# Flight_sensor.net
KiCad netlist of a schematic drawn in Altium Designer
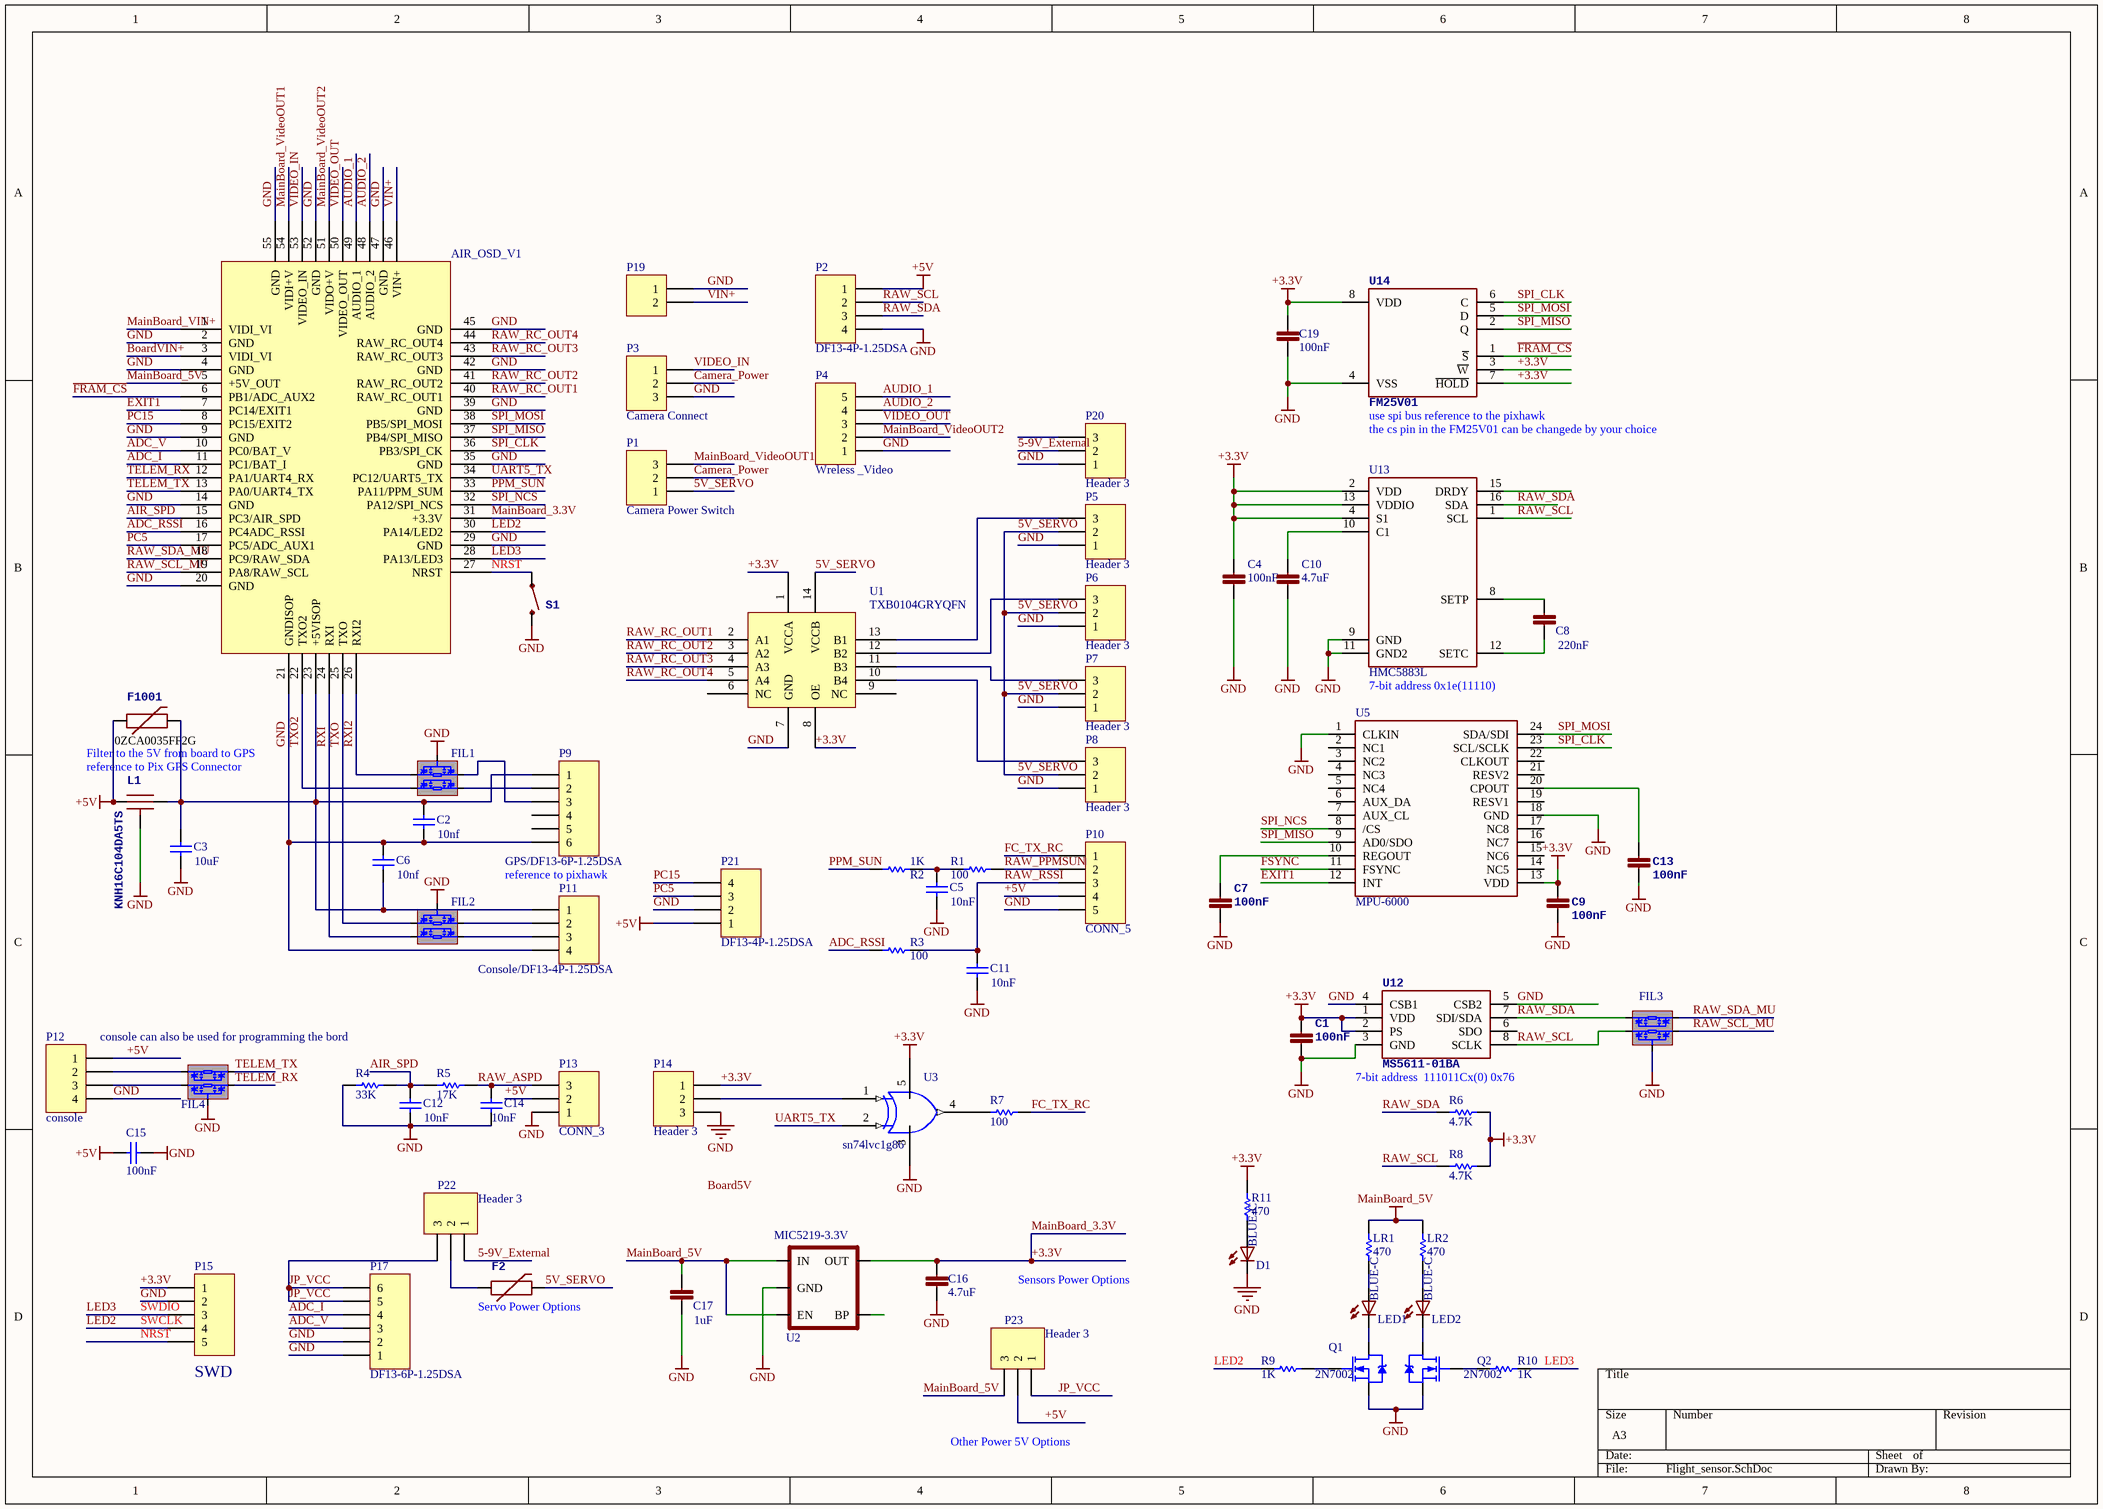
[diagram p0: Flight_sensor.SchDoc]

(export (version "E")
  (design (tool "Eeschema 10.0.6"))
  (components
    (comp (ref "AIR_OSD_V1")
      (value "AIR_OSD_V1")
      (footprint "AIR_OSD_CON")
      (libsource (lib "Schlib") (part "AIR_OSD_V1"))
    )
    (comp (ref "C1") (value "100nF") (footprint "0402-CAP") (libsource (lib "") (part "CAP0402-CAP_1")))
    (comp (ref "C2")
      (value "10nf")
      (footprint "0402-CAP")
      (description "Capacitor")
      (libsource (lib "Miscellaneous Devices") (part "Cap"))
    )
    (comp (ref "C3")
      (value "10uF")
      (footprint "0805")
      (description "Capacitor")
      (libsource (lib "Miscellaneous Devices") (part "Cap"))
    )
    (comp (ref "C4") (value "100nF") (footprint "0402-CAP") (libsource (lib "SparkFun") (part "CAP0402-CAP")))
    (comp (ref "C5")
      (value "10nF")
      (footprint "0402-CAP")
      (description "Capacitor")
      (libsource (lib "Miscellaneous Devices") (part "Cap"))
    )
    (comp (ref "C6")
      (value "10nf")
      (footprint "0402-CAP")
      (description "Capacitor")
      (libsource (lib "Miscellaneous Devices") (part "Cap"))
    )
    (comp (ref "C7") (value "100nF") (footprint "0402-CAP") (libsource (lib "") (part "CAP0402-CAP_1")))
    (comp (ref "C8") (value "220nF") (footprint "0402-CAP") (libsource (lib "SparkFun") (part "CAP0402-CAP")))
    (comp (ref "C9") (value "100nF") (footprint "0402-CAP") (libsource (lib "") (part "CAP0402-CAP_1")))
    (comp (ref "C10") (value "4.7uF") (footprint "0805") (libsource (lib "SparkFun") (part "CAP0805")))
    (comp (ref "C11")
      (value "10nF")
      (footprint "0402-CAP")
      (description "Capacitor")
      (libsource (lib "Miscellaneous Devices") (part "Cap"))
    )
    (comp (ref "C12")
      (value "10nF")
      (footprint "0402-CAP")
      (description "Capacitor")
      (libsource (lib "Miscellaneous Devices") (part "Cap"))
    )
    (comp (ref "C13") (value "100nF") (footprint "0402-CAP") (libsource (lib "") (part "CAP0402-CAP_1")))
    (comp (ref "C14")
      (value "10nF")
      (footprint "0402-CAP")
      (description "Capacitor")
      (libsource (lib "Miscellaneous Devices") (part "Cap"))
    )
    (comp (ref "C15")
      (value "100nF")
      (footprint "0402-CAP")
      (description "Capacitor")
      (libsource (lib "Miscellaneous Devices") (part "Cap"))
    )
    (comp (ref "C16") (value "4.7uF") (footprint "0805") (libsource (lib "SparkFun") (part "CAP0402-CAP")))
    (comp (ref "C17") (value "1uF") (footprint "0805") (libsource (lib "SparkFun") (part "CAP0402-CAP")))
    (comp (ref "C19") (value "100nF") (footprint "0402-CAP") (libsource (lib "") (part "CAP0402-CAP_1")))
    (comp (ref "D1") (value "BLUE-C") (footprint "LED-0603") (libsource (lib "SparkFun") (part "LED0603")))
    (comp (ref "F2")
      (value "0ZCA0035FF2G")
      (footprint "PTC-1206")
      (description "<b>Resettable Fuse PTC</b>\nResettable Fuse. Spark Fun Electronics SKU : COM-08357")
      (fields (field (name ">NAME") "F2"))
      (libsource (lib "pixhawk2") (part "PTCSMD"))
    )
    (comp (ref "F1001")
      (value "0ZCA0035FF2G")
      (footprint "PTC-1206")
      (description "<b>Resettable Fuse PTC</b>\nResettable Fuse. Spark Fun Electronics SKU : COM-08357")
      (fields (field (name ">NAME") "F1001"))
      (libsource (lib "pixhawk2") (part "PTCSMD"))
    )
    (comp (ref "FIL1")
      (value "IP4256CZ5-W,115")
      (footprint "SOT-665")
      (description "IP4256CZ5-W,115 2 channel, 100R, 30pF, RF ESD Filter")
      (fields
        (field (name "MANUFACTURER") "Generic Components")
        (field (name "PUBLISHER") "The OpenPilot Project")
      )
      (libsource (lib "OpenPilot") (part "RF Filter 100R 30pF"))
    )
    (comp (ref "FIL2")
      (value "IP4256CZ5-W,115")
      (footprint "SOT-665")
      (description "IP4256CZ5-W,115 2 channel, 100R, 30pF, RF ESD Filter")
      (fields
        (field (name "MANUFACTURER") "Generic Components")
        (field (name "PUBLISHER") "The OpenPilot Project")
      )
      (libsource (lib "OpenPilot") (part "RF Filter 100R 30pF"))
    )
    (comp (ref "FIL3")
      (value "IP4256CZ5-W,115")
      (footprint "SOT-665")
      (description "IP4256CZ5-W,115 2 channel, 100R, 30pF, RF ESD Filter")
      (fields
        (field (name "MANUFACTURER") "Generic Components")
        (field (name "PUBLISHER") "The OpenPilot Project")
      )
      (libsource (lib "OpenPilot") (part "RF Filter 100R 30pF"))
    )
    (comp (ref "FIL4")
      (value "IP4256CZ5-W,115")
      (footprint "SOT-665")
      (description "IP4256CZ5-W,115 2 channel, 100R, 30pF, RF ESD Filter")
      (fields
        (field (name "MANUFACTURER") "Generic Components")
        (field (name "PUBLISHER") "The OpenPilot Project")
      )
      (libsource (lib "OpenPilot") (part "RF Filter 100R 30pF"))
    )
    (comp (ref "L1")
      (value "KNH16C104DA5TS")
      (footprint "KYOCERA-KNH16-DA")
      (description "Kyocera KNH16C104DA5TS EMI filter")
      (fields (field (name ">NAME") "L1") (field (name ">VALUE") "KNH16C104DA5TS"))
      (libsource (lib "pixhawk2") (part "KNH16C104DA5TS"))
    )
    (comp (ref "LED1") (value "BLUE-C") (footprint "LED-0603") (libsource (lib "SparkFun") (part "LED0603")))
    (comp (ref "LED2") (value "BLUE-C") (footprint "LED-0603") (libsource (lib "SparkFun") (part "LED0603")))
    (comp (ref "LR1")
      (value "470")
      (footprint "0402-RES")
      (description "Resistor")
      (libsource (lib "原理图库") (part "Res1"))
    )
    (comp (ref "LR2")
      (value "470")
      (footprint "0402-RES")
      (description "Resistor")
      (libsource (lib "原理图库") (part "Res1"))
    )
    (comp (ref "P1")
      (value "Camera Power Switch")
      (footprint "3X1-NS")
      (description "Header, 3-Pin")
      (fields (field (name "PUBLISHER") "Altium Limited"))
      (libsource (lib "") (part "Header 3_3"))
    )
    (comp (ref "P2")
      (value "DF13-4P-1.25DSA")
      (footprint "DF13-4P-1.25DSA")
      (description "Header, 4-Pin")
      (fields (field (name "PUBLISHER") "Altium Limited"))
      (libsource (lib "Miscellaneous Connectors") (part "Header 4"))
    )
    (comp (ref "P3")
      (value "Camera Connect")
      (footprint "HDR1X3")
      (description "Header, 3-Pin")
      (fields (field (name "PUBLISHER") "Altium Limited"))
      (libsource (lib "") (part "Header 3_2"))
    )
    (comp (ref "P4")
      (value "Wreless _Video")
      (footprint "HDR1X5")
      (description "Header, 5-Pin")
      (libsource (lib "") (part "Header 5_1"))
    )
    (comp (ref "P5")
      (value "Header 3")
      (footprint "HDR1X3")
      (description "Header, 3-Pin")
      (fields (field (name "PUBLISHER") "Altium Limited"))
      (libsource (lib "Miscellaneous Connectors") (part "Header 3"))
    )
    (comp (ref "P6")
      (value "Header 3")
      (footprint "HDR1X3")
      (description "Header, 3-Pin")
      (fields (field (name "PUBLISHER") "Altium Limited"))
      (libsource (lib "Miscellaneous Connectors") (part "Header 3"))
    )
    (comp (ref "P7")
      (value "Header 3")
      (footprint "HDR1X3")
      (description "Header, 3-Pin")
      (fields (field (name "PUBLISHER") "Altium Limited"))
      (libsource (lib "Miscellaneous Connectors") (part "Header 3"))
    )
    (comp (ref "P8")
      (value "Header 3")
      (footprint "HDR1X3")
      (description "Header, 3-Pin")
      (fields (field (name "PUBLISHER") "Altium Limited"))
      (libsource (lib "Miscellaneous Connectors") (part "Header 3"))
    )
    (comp (ref "P9")
      (value "GPS/DF13-6P-1.25DSA")
      (footprint "PIXHAWK2_DF13-6P-1.25DSA")
      (description "Header, 6-Pin")
      (fields (field (name "PUBLISHER") "Altium Limited"))
      (libsource (lib "") (part "Header 6_1"))
    )
    (comp (ref "P10")
      (value "CONN_5")
      (footprint "DF13-5P-1.25DSA")
      (description "Header, 5-Pin")
      (libsource (lib "Miscellaneous Connectors") (part "Header 5"))
    )
    (comp (ref "P11")
      (value "Console/DF13-4P-1.25DSA")
      (footprint "DF13-4P-1.25DSA")
      (description "Header, 4-Pin")
      (fields (field (name "PUBLISHER") "Altium Limited"))
      (libsource (lib "") (part "Header 4_1"))
    )
    (comp (ref "P12")
      (value "console")
      (footprint "DF13-4P-1.25DSA")
      (description "Header, 4-Pin")
      (fields (field (name "PUBLISHER") "Altium Limited"))
      (libsource (lib "Miscellaneous Connectors") (part "Header 4"))
    )
    (comp (ref "P13")
      (value "CONN_3")
      (footprint "HDR1X3")
      (description "Header, 3-Pin")
      (libsource (lib "Miscellaneous Connectors") (part "Header 3"))
    )
    (comp (ref "P14")
      (value "Header 3")
      (footprint "HDR1X3")
      (description "Header, 3-Pin")
      (fields (field (name "PUBLISHER") "Altium Limited"))
      (libsource (lib "") (part "Header 3_2"))
    )
    (comp (ref "P15")
      (value "SWD")
      (footprint "DF13-5P-1.25DSA")
      (description "Header, 5-Pin")
      (libsource (lib "Miscellaneous Connectors") (part "Header 5"))
    )
    (comp (ref "P17")
      (value "DF13-6P-1.25DSA")
      (footprint "PIXHAWK2_DF13-6P-1.25DSA")
      (description "Header, 6-Pin")
      (libsource (lib "Miscellaneous Connectors") (part "Header 6"))
    )
    (comp (ref "P19")
      (value "Header 2")
      (footprint "HDR1X2")
      (description "接插件")
      (fields (field (name "PUBLISHER") "Altium Limited"))
      (libsource (lib "Miscellaneous Connectors") (part "Header 2"))
    )
    (comp (ref "P20")
      (value "Header 3")
      (footprint "HDR1X3")
      (description "Header, 3-Pin")
      (fields (field (name "PUBLISHER") "Altium Limited"))
      (libsource (lib "Miscellaneous Connectors") (part "Header 3"))
    )
    (comp (ref "P21")
      (value "DF13-4P-1.25DSA")
      (footprint "HDR1X4")
      (description "Header, 4-Pin")
      (fields (field (name "PUBLISHER") "Altium Limited"))
      (libsource (lib "") (part "Header 4_2"))
    )
    (comp (ref "P22")
      (value "Header 3")
      (footprint "0402-S")
      (description "Header, 3-Pin")
      (fields (field (name "PUBLISHER") "Altium Limited"))
      (libsource (lib "") (part "Header 3_1"))
    )
    (comp (ref "P23")
      (value "Header 3")
      (footprint "0402-S")
      (description "Header, 3-Pin")
      (fields (field (name "PUBLISHER") "Altium Limited"))
      (libsource (lib "") (part "Header 3_1"))
    )
    (comp (ref "Q1")
      (value "2N7002")
      (footprint "2N7002")
      (description "CQ-IRF840")
      (libsource (lib "晶体管") (part "IRF840"))
    )
    (comp (ref "Q2")
      (value "2N7002")
      (footprint "2N7002")
      (description "CQ-IRF840")
      (libsource (lib "晶体管") (part "IRF840"))
    )
    (comp (ref "R1")
      (value "100")
      (footprint "0402-RES")
      (description "Resistor")
      (libsource (lib "Miscellaneous Devices") (part "Res1"))
    )
    (comp (ref "R2")
      (value "1K")
      (footprint "0402-RES")
      (description "Resistor")
      (libsource (lib "Miscellaneous Devices") (part "Res1"))
    )
    (comp (ref "R3")
      (value "100")
      (footprint "0402-RES")
      (description "Resistor")
      (libsource (lib "Miscellaneous Devices") (part "Res1"))
    )
    (comp (ref "R4")
      (value "33K")
      (footprint "0402-RES")
      (description "Resistor")
      (libsource (lib "Miscellaneous Devices") (part "Res1"))
    )
    (comp (ref "R5")
      (value "17K")
      (footprint "0402-RES")
      (description "Resistor")
      (libsource (lib "Miscellaneous Devices") (part "Res1"))
    )
    (comp (ref "R6")
      (value "4.7K")
      (footprint "0402-RES")
      (description "Resistor")
      (libsource (lib "Miscellaneous Devices") (part "Res1"))
    )
    (comp (ref "R7")
      (value "100")
      (footprint "0402-RES")
      (description "Resistor")
      (libsource (lib "原理图库") (part "Res1"))
    )
    (comp (ref "R8")
      (value "4.7K")
      (footprint "0402-RES")
      (description "Resistor")
      (libsource (lib "Miscellaneous Devices") (part "Res1"))
    )
    (comp (ref "R9")
      (value "1K")
      (footprint "0402-RES")
      (description "Resistor")
      (libsource (lib "Miscellaneous Devices") (part "Res1"))
    )
    (comp (ref "R10")
      (value "1K")
      (footprint "0402-RES")
      (description "Resistor")
      (libsource (lib "Miscellaneous Devices") (part "Res1"))
    )
    (comp (ref "R11")
      (value "470")
      (footprint "0402-RES")
      (description "Resistor")
      (libsource (lib "原理图库") (part "Res1"))
    )
    (comp (ref "S1")
      (value "RESET")
      (footprint "EVQP7J01K")
      (libsource (lib "pixhawk2") (part "SWITCH-MOMENTARY-2"))
    )
    (comp (ref "U1")
      (value "TXB0104GRYQFN")
      (footprint "RGY(S-PVQFN-N14)")
      (libsource (lib "Schlib") (part "TXB0104UQFN"))
    )
    (comp (ref "U2")
      (value "MIC5219-3.3V")
      (footprint "SOT23-5")
      (libsource (lib "SparkFun") (part "V_REG_LDOSMD"))
    )
    (comp (ref "U3") (value "sn74lvc1g86") (libsource (lib "FlightSensorPrj") (part "sn74lvc1g86")))
    (comp (ref "U5")
      (value "MPU-6000")
      (footprint "MPU6000")
      (libsource (lib "3DRobotics_Master_Library") (part "MPU-3000"))
    )
    (comp (ref "U12")
      (value "MS5611-01BA")
      (footprint "MS5611-01BA")
      (libsource (lib "3DRobotics") (part "MS5611-01BA"))
    )
    (comp (ref "U13")
      (value "HMC5883L")
      (footprint "LPCC16")
      (libsource (lib "3DRobotics") (part "HMC5883L"))
    )
    (comp (ref "U14")
      (value "FM25V01")
      (footprint "SO08")
      (description "<b>FM25V01 128Kb Serial 3V F-RAM Memory</b>")
      (fields
        (field (name "PARTNO") "FM25V01-G")
        (field (name ">NAME") "U14")
        (field (name ">VALUE") "FM25V01")
      )
      (libsource (lib "pixhawk2") (part "FM25V01"))
    )
  )
  (nets
    (net (code "1") (name "+3.3V") (class "Default")
      (node (ref "AIR_OSD_V1") (pin "31") (pinfunction "+3.3V_31") (pintype "passive"))
      (node (ref "C1") (pin "2") (pinfunction "2_2") (pintype "passive"))
      (node (ref "C16") (pin "1") (pinfunction "1_1") (pintype "passive"))
      (node (ref "C19") (pin "2") (pinfunction "2_2") (pintype "passive"))
      (node (ref "C4") (pin "1") (pinfunction "1_1") (pintype "passive"))
      (node (ref "C9") (pin "2") (pinfunction "2_2") (pintype "passive"))
      (node (ref "P14") (pin "1") (pinfunction "1_1") (pintype "passive"))
      (node (ref "P15") (pin "1") (pinfunction "1_1") (pintype "passive"))
      (node (ref "R11") (pin "2") (pinfunction "2_2") (pintype "passive"))
      (node (ref "R6") (pin "1") (pinfunction "1_1") (pintype "passive"))
      (node (ref "R8") (pin "1") (pinfunction "1_1") (pintype "passive"))
      (node (ref "U1") (pin "1") (pinfunction "VCCA_1") (pintype "passive"))
      (node (ref "U1") (pin "8") (pinfunction "OE_8") (pintype "passive"))
      (node (ref "U12") (pin "1") (pinfunction "VDD_1") (pintype "passive"))
      (node (ref "U12") (pin "2") (pinfunction "PS_2") (pintype "passive"))
      (node (ref "U13") (pin "13") (pinfunction "VDDIO_13") (pintype "passive"))
      (node (ref "U13") (pin "2") (pinfunction "VDD_2") (pintype "passive"))
      (node (ref "U13") (pin "4") (pinfunction "S1_4") (pintype "passive"))
      (node (ref "U14") (pin "3") (pinfunction "~{W}_3") (pintype "passive"))
      (node (ref "U14") (pin "7") (pinfunction "~{HOLD}_7") (pintype "passive"))
      (node (ref "U14") (pin "8") (pinfunction "VDD_8") (pintype "passive"))
      (node (ref "U2") (pin "5") (pinfunction "OUT_5") (pintype "passive"))
      (node (ref "U3") (pin "5") (pinfunction "VDD_5") (pintype "power_in"))
      (node (ref "U5") (pin "13") (pinfunction "VDD_13") (pintype "passive"))
    )
    (net (code "2") (name "+5V") (class "Default")
      (node (ref "C15") (pin "2") (pinfunction "2_2") (pintype "passive"))
      (node (ref "F1001") (pin "1") (pinfunction "1_1") (pintype "passive"))
      (node (ref "L1") (pin "P$1") (pinfunction "P$1_P$1") (pintype "passive"))
      (node (ref "P10") (pin "4") (pinfunction "4_4") (pintype "passive"))
      (node (ref "P12") (pin "1") (pinfunction "1_1") (pintype "passive"))
      (node (ref "P13") (pin "2") (pinfunction "2_2") (pintype "passive"))
      (node (ref "P2") (pin "1") (pinfunction "1_1") (pintype "passive"))
      (node (ref "P21") (pin "1") (pinfunction "1_1") (pintype "passive"))
      (node (ref "P23") (pin "2") (pinfunction "2_2") (pintype "passive"))
    )
    (net (code "3") (name "/5-9V_External") (class "Default")
      (node (ref "P20") (pin "2") (pinfunction "2_2") (pintype "passive"))
      (node (ref "P22") (pin "1") (pinfunction "1_1") (pintype "passive"))
    )
    (net (code "4") (name "/5V_SERVO") (class "Default")
      (node (ref "F2") (pin "2") (pinfunction "2_2") (pintype "passive"))
      (node (ref "P1") (pin "1") (pinfunction "1_1") (pintype "passive"))
      (node (ref "P5") (pin "2") (pinfunction "2_2") (pintype "passive"))
      (node (ref "P6") (pin "2") (pinfunction "2_2") (pintype "passive"))
      (node (ref "P7") (pin "2") (pinfunction "2_2") (pintype "passive"))
      (node (ref "P8") (pin "2") (pinfunction "2_2") (pintype "passive"))
      (node (ref "U1") (pin "14") (pinfunction "VCCB_14") (pintype "passive"))
    )
    (net (code "5") (name "/ADC_I") (class "Default")
      (node (ref "AIR_OSD_V1") (pin "11") (pinfunction "PC1/BAT_I_11") (pintype "passive"))
      (node (ref "P17") (pin "4") (pinfunction "4_4") (pintype "passive"))
    )
    (net (code "6") (name "/ADC_RSSI") (class "Default")
      (node (ref "AIR_OSD_V1") (pin "16") (pinfunction "PC4ADC_RSSI_16") (pintype "passive"))
      (node (ref "R3") (pin "2") (pinfunction "2_2") (pintype "passive"))
    )
    (net (code "7") (name "/ADC_V") (class "Default")
      (node (ref "AIR_OSD_V1") (pin "10") (pinfunction "PC0/BAT_V_10") (pintype "passive"))
      (node (ref "P17") (pin "3") (pinfunction "3_3") (pintype "passive"))
    )
    (net (code "8") (name "/AIR_SPD") (class "Default")
      (node (ref "AIR_OSD_V1") (pin "15") (pinfunction "PC3/AIR_SPD_15") (pintype "passive"))
      (node (ref "C12") (pin "2") (pinfunction "2_2") (pintype "passive"))
      (node (ref "R4") (pin "1") (pinfunction "1_1") (pintype "passive"))
      (node (ref "R5") (pin "2") (pinfunction "2_2") (pintype "passive"))
    )
    (net (code "9") (name "/AUDIO_1") (class "Default")
      (node (ref "AIR_OSD_V1") (pin "49") (pinfunction "AUDIO_1_49") (pintype "passive"))
      (node (ref "P4") (pin "5") (pinfunction "5_5") (pintype "passive"))
    )
    (net (code "10") (name "/AUDIO_2") (class "Default")
      (node (ref "AIR_OSD_V1") (pin "48") (pinfunction "AUDIO_2_48") (pintype "passive"))
      (node (ref "P4") (pin "4") (pinfunction "4_4") (pintype "passive"))
    )
    (net (code "12") (name "/BoardVIN+") (class "Default")
      (node (ref "AIR_OSD_V1") (pin "3") (pinfunction "VIDI_VI_3") (pintype "passive"))
    )
    (net (code "13") (name "/Camera_Power") (class "Default")
      (node (ref "P1") (pin "2") (pinfunction "2_2") (pintype "passive"))
      (node (ref "P3") (pin "2") (pinfunction "2_2") (pintype "passive"))
    )
    (net (code "14") (name "/EXIT1") (class "Default")
      (node (ref "AIR_OSD_V1") (pin "7") (pinfunction "PC14/EXIT1_7") (pintype "passive"))
      (node (ref "U5") (pin "12") (pinfunction "INT_12") (pintype "passive"))
    )
    (net (code "15") (name "/FC_TX_RC") (class "Default")
      (node (ref "P10") (pin "1") (pinfunction "1_1") (pintype "passive"))
      (node (ref "R7") (pin "1") (pinfunction "1_1") (pintype "passive"))
    )
    (net (code "16") (name "/FSYNC") (class "Default")
      (node (ref "U5") (pin "11") (pinfunction "FSYNC_11") (pintype "passive"))
    )
    (net (code "17") (name "/JP_VCC") (class "Default")
      (node (ref "P17") (pin "5") (pinfunction "5_5") (pintype "passive"))
      (node (ref "P17") (pin "6") (pinfunction "6_6") (pintype "passive"))
      (node (ref "P22") (pin "3") (pinfunction "3_3") (pintype "passive"))
      (node (ref "P23") (pin "1") (pinfunction "1_1") (pintype "passive"))
    )
    (net (code "18") (name "/LED2") (class "Default")
      (node (ref "AIR_OSD_V1") (pin "30") (pinfunction "PA14/LED2_30") (pintype "passive"))
      (node (ref "P15") (pin "4") (pinfunction "4_4") (pintype "passive"))
      (node (ref "R9") (pin "2") (pinfunction "2_2") (pintype "passive"))
    )
    (net (code "19") (name "/LED3") (class "Default")
      (node (ref "AIR_OSD_V1") (pin "28") (pinfunction "PA13/LED3_28") (pintype "passive"))
      (node (ref "P15") (pin "3") (pinfunction "3_3") (pintype "passive"))
      (node (ref "R10") (pin "1") (pinfunction "1_1") (pintype "passive"))
    )
    (net (code "20") (name "/MainBoard_VIN+") (class "Default")
      (node (ref "AIR_OSD_V1") (pin "1") (pinfunction "VIDI_VI_1") (pintype "passive"))
    )
    (net (code "21") (name "/MainBoard_VideoOUT1") (class "Default")
      (node (ref "AIR_OSD_V1") (pin "54") (pinfunction "VIDI+V_54") (pintype "passive"))
      (node (ref "P1") (pin "3") (pinfunction "3_3") (pintype "passive"))
    )
    (net (code "22") (name "/MainBoard_VideoOUT2") (class "Default")
      (node (ref "AIR_OSD_V1") (pin "51") (pinfunction "VIDO+V_51") (pintype "passive"))
      (node (ref "P4") (pin "2") (pinfunction "2_2") (pintype "passive"))
    )
    (net (code "23") (name "/NRST") (class "Default")
      (node (ref "AIR_OSD_V1") (pin "27") (pinfunction "NRST_27") (pintype "passive"))
      (node (ref "P15") (pin "5") (pinfunction "5_5") (pintype "passive"))
      (node (ref "S1") (pin "A1") (pinfunction "1_A1") (pintype "passive"))
    )
    (net (code "24") (name "/PC5") (class "Default")
      (node (ref "AIR_OSD_V1") (pin "17") (pinfunction "PC5/ADC_AUX1_17") (pintype "passive"))
      (node (ref "P21") (pin "3") (pinfunction "3_3") (pintype "passive"))
    )
    (net (code "25") (name "/PC15") (class "Default")
      (node (ref "AIR_OSD_V1") (pin "8") (pinfunction "PC15/EXIT2_8") (pintype "passive"))
      (node (ref "P21") (pin "4") (pinfunction "4_4") (pintype "passive"))
    )
    (net (code "26") (name "/PPM_SUN") (class "Default")
      (node (ref "AIR_OSD_V1") (pin "33") (pinfunction "PA11/PPM_SUM_33") (pintype "passive"))
      (node (ref "R2") (pin "2") (pinfunction "2_2") (pintype "passive"))
    )
    (net (code "27") (name "/RAW_ASPD") (class "Default")
      (node (ref "C14") (pin "2") (pinfunction "2_2") (pintype "passive"))
      (node (ref "P13") (pin "3") (pinfunction "3_3") (pintype "passive"))
      (node (ref "R5") (pin "1") (pinfunction "1_1") (pintype "passive"))
    )
    (net (code "28") (name "/RAW_PPMSUN") (class "Default")
      (node (ref "P10") (pin "2") (pinfunction "2_2") (pintype "passive"))
      (node (ref "R1") (pin "1") (pinfunction "1_1") (pintype "passive"))
    )
    (net (code "29") (name "/RAW_RC_OUT1") (class "Default")
      (node (ref "AIR_OSD_V1") (pin "40") (pinfunction "RAW_RC_OUT1_40") (pintype "passive"))
      (node (ref "U1") (pin "2") (pinfunction "A1_2") (pintype "passive"))
    )
    (net (code "30") (name "/RAW_RC_OUT2") (class "Default")
      (node (ref "AIR_OSD_V1") (pin "41") (pinfunction "RAW_RC_OUT2_41") (pintype "passive"))
      (node (ref "U1") (pin "3") (pinfunction "A2_3") (pintype "passive"))
    )
    (net (code "31") (name "/RAW_RC_OUT3") (class "Default")
      (node (ref "AIR_OSD_V1") (pin "43") (pinfunction "RAW_RC_OUT3_43") (pintype "passive"))
      (node (ref "U1") (pin "4") (pinfunction "A3_4") (pintype "passive"))
    )
    (net (code "32") (name "/RAW_RC_OUT4") (class "Default")
      (node (ref "AIR_OSD_V1") (pin "44") (pinfunction "RAW_RC_OUT4_44") (pintype "passive"))
      (node (ref "U1") (pin "5") (pinfunction "A4_5") (pintype "passive"))
    )
    (net (code "33") (name "/RAW_RSSI") (class "Default")
      (node (ref "C11") (pin "2") (pinfunction "2_2") (pintype "passive"))
      (node (ref "P10") (pin "3") (pinfunction "3_3") (pintype "passive"))
      (node (ref "R3") (pin "1") (pinfunction "1_1") (pintype "passive"))
    )
    (net (code "34") (name "/RAW_SCL") (class "Default")
      (node (ref "FIL3") (pin "5") (pinfunction "5_5") (pintype "passive"))
      (node (ref "P2") (pin "2") (pinfunction "2_2") (pintype "passive"))
      (node (ref "R8") (pin "2") (pinfunction "2_2") (pintype "passive"))
      (node (ref "U12") (pin "8") (pinfunction "SCLK_8") (pintype "passive"))
      (node (ref "U13") (pin "1") (pinfunction "SCL_1") (pintype "passive"))
    )
    (net (code "35") (name "/RAW_SCL_MU") (class "Default")
      (node (ref "AIR_OSD_V1") (pin "19") (pinfunction "PA8/RAW_SCL_19") (pintype "passive"))
      (node (ref "FIL3") (pin "1") (pinfunction "1_1") (pintype "passive"))
    )
    (net (code "36") (name "/RAW_SDA") (class "Default")
      (node (ref "FIL3") (pin "4") (pinfunction "4_4") (pintype "passive"))
      (node (ref "P2") (pin "3") (pinfunction "3_3") (pintype "passive"))
      (node (ref "R6") (pin "2") (pinfunction "2_2") (pintype "passive"))
      (node (ref "U12") (pin "7") (pinfunction "SDI/SDA_7") (pintype "passive"))
      (node (ref "U13") (pin "16") (pinfunction "SDA_16") (pintype "passive"))
    )
    (net (code "37") (name "/RAW_SDA_MU") (class "Default")
      (node (ref "AIR_OSD_V1") (pin "18") (pinfunction "PC9/RAW_SDA_18") (pintype "passive"))
      (node (ref "FIL3") (pin "3") (pinfunction "3_3") (pintype "passive"))
    )
    (net (code "38") (name "/RXI") (class "Default")
      (node (ref "AIR_OSD_V1") (pin "24") (pinfunction "RXI_24") (pintype "passive"))
      (node (ref "FIL2") (pin "3") (pinfunction "3_3") (pintype "passive"))
    )
    (net (code "39") (name "/RXI2") (class "Default")
      (node (ref "AIR_OSD_V1") (pin "26") (pinfunction "RXI2_26") (pintype "passive"))
      (node (ref "FIL1") (pin "1") (pinfunction "1_1") (pintype "passive"))
    )
    (net (code "40") (name "/SPI_CLK") (class "Default")
      (node (ref "AIR_OSD_V1") (pin "36") (pinfunction "PB3/SPI_CK_36") (pintype "passive"))
      (node (ref "U14") (pin "6") (pinfunction "C_6") (pintype "passive"))
      (node (ref "U5") (pin "23") (pinfunction "SCL/SCLK_23") (pintype "passive"))
    )
    (net (code "41") (name "/SPI_MISO") (class "Default")
      (node (ref "AIR_OSD_V1") (pin "37") (pinfunction "PB4/SPI_MISO_37") (pintype "passive"))
      (node (ref "U14") (pin "2") (pinfunction "Q_2") (pintype "passive"))
      (node (ref "U5") (pin "9") (pinfunction "AD0/SDO_9") (pintype "passive"))
    )
    (net (code "42") (name "/SPI_MOSI") (class "Default")
      (node (ref "AIR_OSD_V1") (pin "38") (pinfunction "PB5/SPI_MOSI_38") (pintype "passive"))
      (node (ref "U14") (pin "5") (pinfunction "D_5") (pintype "passive"))
      (node (ref "U5") (pin "24") (pinfunction "SDA/SDI_24") (pintype "passive"))
    )
    (net (code "43") (name "/SPI_NCS") (class "Default")
      (node (ref "AIR_OSD_V1") (pin "32") (pinfunction "PA12/SPI_NCS_32") (pintype "passive"))
      (node (ref "U5") (pin "8") (pinfunction "/CS_8") (pintype "passive"))
    )
    (net (code "44") (name "/TELEM_RX") (class "Default")
      (node (ref "AIR_OSD_V1") (pin "12") (pinfunction "PA1/UART4_RX_12") (pintype "passive"))
      (node (ref "FIL4") (pin "1") (pinfunction "1_1") (pintype "passive"))
    )
    (net (code "45") (name "/TELEM_TX") (class "Default")
      (node (ref "AIR_OSD_V1") (pin "13") (pinfunction "PA0/UART4_TX_13") (pintype "passive"))
      (node (ref "FIL4") (pin "3") (pinfunction "3_3") (pintype "passive"))
    )
    (net (code "46") (name "/TXO") (class "Default")
      (node (ref "AIR_OSD_V1") (pin "25") (pinfunction "TXO_25") (pintype "passive"))
      (node (ref "FIL2") (pin "1") (pinfunction "1_1") (pintype "passive"))
    )
    (net (code "47") (name "/TXO2") (class "Default")
      (node (ref "AIR_OSD_V1") (pin "22") (pinfunction "TXO2_22") (pintype "passive"))
      (node (ref "FIL1") (pin "3") (pinfunction "3_3") (pintype "passive"))
    )
    (net (code "48") (name "/UART5_TX") (class "Default")
      (node (ref "AIR_OSD_V1") (pin "34") (pinfunction "PC12/UART5_TX_34") (pintype "passive"))
      (node (ref "U3") (pin "2") (pintype "input"))
    )
    (net (code "49") (name "/VIDEO_IN") (class "Default")
      (node (ref "AIR_OSD_V1") (pin "53") (pinfunction "VIDEO_IN_53") (pintype "passive"))
      (node (ref "P3") (pin "1") (pinfunction "1_1") (pintype "passive"))
    )
    (net (code "50") (name "/VIDEO_OUT") (class "Default")
      (node (ref "AIR_OSD_V1") (pin "50") (pinfunction "VIDEO_OUT_50") (pintype "passive"))
      (node (ref "P4") (pin "3") (pinfunction "3_3") (pintype "passive"))
    )
    (net (code "51") (name "/VIN+") (class "Default")
      (node (ref "AIR_OSD_V1") (pin "46") (pinfunction "VIN+_46") (pintype "passive"))
      (node (ref "P19") (pin "2") (pinfunction "2_2") (pintype "passive"))
    )
    (net (code "52") (name "/~{FRAM_CS}") (class "Default")
      (node (ref "AIR_OSD_V1") (pin "6") (pinfunction "PB1/ADC_AUX2_6") (pintype "passive"))
      (node (ref "U14") (pin "1") (pinfunction "~{S}_1") (pintype "passive"))
    )
    (net (code "53") (name "GND") (class "Default")
      (node (ref "AIR_OSD_V1") (pin "14") (pinfunction "GND_14") (pintype "passive"))
      (node (ref "AIR_OSD_V1") (pin "2") (pinfunction "GND_2") (pintype "passive"))
      (node (ref "AIR_OSD_V1") (pin "20") (pinfunction "GND_20") (pintype "passive"))
      (node (ref "AIR_OSD_V1") (pin "21") (pinfunction "GNDISOP_21") (pintype "passive"))
      (node (ref "AIR_OSD_V1") (pin "29") (pinfunction "GND_29") (pintype "passive"))
      (node (ref "AIR_OSD_V1") (pin "35") (pinfunction "GND_35") (pintype "passive"))
      (node (ref "AIR_OSD_V1") (pin "39") (pinfunction "GND_39") (pintype "passive"))
      (node (ref "AIR_OSD_V1") (pin "4") (pinfunction "GND_4") (pintype "passive"))
      (node (ref "AIR_OSD_V1") (pin "42") (pinfunction "GND_42") (pintype "passive"))
      (node (ref "AIR_OSD_V1") (pin "45") (pinfunction "GND_45") (pintype "passive"))
      (node (ref "AIR_OSD_V1") (pin "47") (pinfunction "GND_47") (pintype "passive"))
      (node (ref "AIR_OSD_V1") (pin "52") (pinfunction "GND_52") (pintype "passive"))
      (node (ref "AIR_OSD_V1") (pin "55") (pinfunction "GND_55") (pintype "passive"))
      (node (ref "AIR_OSD_V1") (pin "9") (pinfunction "GND_9") (pintype "passive"))
      (node (ref "C1") (pin "1") (pinfunction "1_1") (pintype "passive"))
      (node (ref "C10") (pin "2") (pinfunction "2_2") (pintype "passive"))
      (node (ref "C11") (pin "1") (pinfunction "1_1") (pintype "passive"))
      (node (ref "C12") (pin "1") (pinfunction "1_1") (pintype "passive"))
      (node (ref "C13") (pin "1") (pinfunction "1_1") (pintype "passive"))
      (node (ref "C14") (pin "1") (pinfunction "1_1") (pintype "passive"))
      (node (ref "C15") (pin "1") (pinfunction "1_1") (pintype "passive"))
      (node (ref "C16") (pin "2") (pinfunction "2_2") (pintype "passive"))
      (node (ref "C17") (pin "2") (pinfunction "2_2") (pintype "passive"))
      (node (ref "C19") (pin "1") (pinfunction "1_1") (pintype "passive"))
      (node (ref "C2") (pin "1") (pinfunction "1_1") (pintype "passive"))
      (node (ref "C3") (pin "1") (pinfunction "1_1") (pintype "passive"))
      (node (ref "C4") (pin "2") (pinfunction "2_2") (pintype "passive"))
      (node (ref "C5") (pin "1") (pinfunction "1_1") (pintype "passive"))
      (node (ref "C6") (pin "2") (pinfunction "2_2") (pintype "passive"))
      (node (ref "C7") (pin "1") (pinfunction "1_1") (pintype "passive"))
      (node (ref "C9") (pin "1") (pinfunction "1_1") (pintype "passive"))
      (node (ref "D1") (pin "C") (pinfunction "C_C") (pintype "passive"))
      (node (ref "FIL1") (pin "2") (pinfunction "PAD_2") (pintype "passive"))
      (node (ref "FIL2") (pin "2") (pinfunction "PAD_2") (pintype "passive"))
      (node (ref "FIL3") (pin "2") (pinfunction "PAD_2") (pintype "passive"))
      (node (ref "FIL4") (pin "2") (pinfunction "PAD_2") (pintype "passive"))
      (node (ref "L1") (pin "P$3_P$4_P$5") (pinfunction "P$3_P$3_P$4_P$5") (pintype "passive"))
      (node (ref "P10") (pin "5") (pinfunction "5_5") (pintype "passive"))
      (node (ref "P11") (pin "4") (pinfunction "4_4") (pintype "passive"))
      (node (ref "P12") (pin "4") (pinfunction "4_4") (pintype "passive"))
      (node (ref "P13") (pin "1") (pinfunction "1_1") (pintype "passive"))
      (node (ref "P14") (pin "3") (pinfunction "3_3") (pintype "passive"))
      (node (ref "P15") (pin "2") (pinfunction "2_2") (pintype "passive"))
      (node (ref "P17") (pin "1") (pinfunction "1_1") (pintype "passive"))
      (node (ref "P17") (pin "2") (pinfunction "2_2") (pintype "passive"))
      (node (ref "P19") (pin "1") (pinfunction "1_1") (pintype "passive"))
      (node (ref "P2") (pin "4") (pinfunction "4_4") (pintype "passive"))
      (node (ref "P20") (pin "1") (pinfunction "1_1") (pintype "passive"))
      (node (ref "P21") (pin "2") (pinfunction "2_2") (pintype "passive"))
      (node (ref "P3") (pin "3") (pinfunction "3_3") (pintype "passive"))
      (node (ref "P4") (pin "1") (pinfunction "1_1") (pintype "passive"))
      (node (ref "P5") (pin "1") (pinfunction "1_1") (pintype "passive"))
      (node (ref "P6") (pin "1") (pinfunction "1_1") (pintype "passive"))
      (node (ref "P7") (pin "1") (pinfunction "1_1") (pintype "passive"))
      (node (ref "P8") (pin "1") (pinfunction "1_1") (pintype "passive"))
      (node (ref "P9") (pin "6") (pinfunction "6_6") (pintype "passive"))
      (node (ref "Q1") (pin "3") (pinfunction "S_3") (pintype "passive"))
      (node (ref "Q2") (pin "3") (pinfunction "S_3") (pintype "passive"))
      (node (ref "R4") (pin "2") (pinfunction "2_2") (pintype "passive"))
      (node (ref "S1") (pin "B3") (pinfunction "2_B3") (pintype "passive"))
      (node (ref "U1") (pin "7") (pinfunction "GND_7") (pintype "passive"))
      (node (ref "U12") (pin "3") (pinfunction "GND_3") (pintype "passive"))
      (node (ref "U12") (pin "4") (pinfunction "CSB1_4") (pintype "passive"))
      (node (ref "U12") (pin "5") (pinfunction "CSB2_5") (pintype "passive"))
      (node (ref "U13") (pin "11") (pinfunction "GND2_11") (pintype "passive"))
      (node (ref "U13") (pin "9") (pinfunction "GND_9") (pintype "passive"))
      (node (ref "U14") (pin "4") (pinfunction "VSS_4") (pintype "passive"))
      (node (ref "U2") (pin "2") (pinfunction "GND_2") (pintype "passive"))
      (node (ref "U3") (pin "3") (pinfunction "GND_3") (pintype "power_in"))
      (node (ref "U5") (pin "1") (pinfunction "CLKIN_1") (pintype "passive"))
      (node (ref "U5") (pin "18") (pinfunction "GND_18") (pintype "passive"))
    )
    (net (code "54") (name "MainBoard_5V") (class "Default")
      (node (ref "AIR_OSD_V1") (pin "5") (pinfunction "+5V_OUT_5") (pintype "passive"))
      (node (ref "C17") (pin "1") (pinfunction "1_1") (pintype "passive"))
      (node (ref "LR1") (pin "2") (pinfunction "2_2") (pintype "passive"))
      (node (ref "LR2") (pin "2") (pinfunction "2_2") (pintype "passive"))
      (node (ref "P23") (pin "3") (pinfunction "3_3") (pintype "passive"))
      (node (ref "U2") (pin "1") (pinfunction "IN_1") (pintype "passive"))
      (node (ref "U2") (pin "3") (pinfunction "EN_3") (pintype "passive"))
    )
    (net (code "55") (name "Net-(AIR_OSD_V1-+5VISOP)") (class "Default")
      (node (ref "AIR_OSD_V1") (pin "23") (pinfunction "+5VISOP_23") (pintype "passive"))
      (node (ref "C2") (pin "2") (pinfunction "2_2") (pintype "passive"))
      (node (ref "C3") (pin "2") (pinfunction "2_2") (pintype "passive"))
      (node (ref "C6") (pin "1") (pinfunction "1_1") (pintype "passive"))
      (node (ref "F1001") (pin "2") (pinfunction "2_2") (pintype "passive"))
      (node (ref "L1") (pin "P$2") (pinfunction "P$2_P$2") (pintype "passive"))
      (node (ref "P11") (pin "1") (pinfunction "1_1") (pintype "passive"))
      (node (ref "P9") (pin "1") (pinfunction "1_1") (pintype "passive"))
    )
    (net (code "56") (name "Net-(C5-Pad2)") (class "Default")
      (node (ref "C5") (pin "2") (pinfunction "2_2") (pintype "passive"))
      (node (ref "R1") (pin "2") (pinfunction "2_2") (pintype "passive"))
      (node (ref "R2") (pin "1") (pinfunction "1_1") (pintype "passive"))
    )
    (net (code "57") (name "Net-(D1-PadA)") (class "Default")
      (node (ref "D1") (pin "A") (pinfunction "A_A") (pintype "passive"))
      (node (ref "R11") (pin "1") (pinfunction "1_1") (pintype "passive"))
    )
    (net (code "58") (name "Net-(F2-Pad1)") (class "Default")
      (node (ref "F2") (pin "1") (pinfunction "1_1") (pintype "passive"))
      (node (ref "P22") (pin "2") (pinfunction "2_2") (pintype "passive"))
    )
    (net (code "59") (name "Net-(FIL1-Pad4)") (class "Default")
      (node (ref "FIL1") (pin "4") (pinfunction "4_4") (pintype "passive"))
      (node (ref "P9") (pin "2") (pinfunction "2_2") (pintype "passive"))
    )
    (net (code "60") (name "Net-(FIL1-Pad5)") (class "Default")
      (node (ref "FIL1") (pin "5") (pinfunction "5_5") (pintype "passive"))
      (node (ref "P9") (pin "3") (pinfunction "3_3") (pintype "passive"))
    )
    (net (code "61") (name "Net-(FIL2-Pad4)") (class "Default")
      (node (ref "FIL2") (pin "4") (pinfunction "4_4") (pintype "passive"))
      (node (ref "P11") (pin "3") (pinfunction "3_3") (pintype "passive"))
    )
    (net (code "62") (name "Net-(FIL2-Pad5)") (class "Default")
      (node (ref "FIL2") (pin "5") (pinfunction "5_5") (pintype "passive"))
      (node (ref "P11") (pin "2") (pinfunction "2_2") (pintype "passive"))
    )
    (net (code "63") (name "Net-(FIL4-Pad4)") (class "Default")
      (node (ref "FIL4") (pin "4") (pinfunction "4_4") (pintype "passive"))
      (node (ref "P12") (pin "2") (pinfunction "2_2") (pintype "passive"))
    )
    (net (code "64") (name "Net-(FIL4-Pad5)") (class "Default")
      (node (ref "FIL4") (pin "5") (pinfunction "5_5") (pintype "passive"))
      (node (ref "P12") (pin "3") (pinfunction "3_3") (pintype "passive"))
    )
    (net (code "65") (name "Net-(LED1-PadA)") (class "Default")
      (node (ref "LED1") (pin "A") (pinfunction "A_A") (pintype "passive"))
      (node (ref "LR1") (pin "1") (pinfunction "1_1") (pintype "passive"))
    )
    (net (code "66") (name "Net-(LED2-PadA)") (class "Default")
      (node (ref "LED2") (pin "A") (pinfunction "A_A") (pintype "passive"))
      (node (ref "LR2") (pin "1") (pinfunction "1_1") (pintype "passive"))
    )
    (net (code "67") (name "Net-(P14-Pad2)") (class "Default")
      (node (ref "P14") (pin "2") (pinfunction "2_2") (pintype "passive"))
      (node (ref "U3") (pin "1") (pintype "input"))
    )
    (net (code "68") (name "Net-(Q1-D)") (class "Default")
      (node (ref "LED1") (pin "C") (pinfunction "C_C") (pintype "passive"))
      (node (ref "Q1") (pin "2") (pinfunction "D_2") (pintype "passive"))
    )
    (net (code "69") (name "Net-(Q1-G)") (class "Default")
      (node (ref "Q1") (pin "1") (pinfunction "G_1") (pintype "passive"))
      (node (ref "R9") (pin "1") (pinfunction "1_1") (pintype "passive"))
    )
    (net (code "70") (name "Net-(Q2-D)") (class "Default")
      (node (ref "LED2") (pin "C") (pinfunction "C_C") (pintype "passive"))
      (node (ref "Q2") (pin "2") (pinfunction "D_2") (pintype "passive"))
    )
    (net (code "71") (name "Net-(Q2-G)") (class "Default")
      (node (ref "Q2") (pin "1") (pinfunction "G_1") (pintype "passive"))
      (node (ref "R10") (pin "2") (pinfunction "2_2") (pintype "passive"))
    )
    (net (code "72") (name "Net-(R7-Pad2)") (class "Default")
      (node (ref "R7") (pin "2") (pinfunction "2_2") (pintype "passive"))
      (node (ref "U3") (pin "4") (pintype "output"))
    )
    (net (code "73") (name "Net-(U1-B1)") (class "Default")
      (node (ref "P5") (pin "3") (pinfunction "3_3") (pintype "passive"))
      (node (ref "U1") (pin "13") (pinfunction "B1_13") (pintype "passive"))
    )
    (net (code "74") (name "Net-(U1-B2)") (class "Default")
      (node (ref "P6") (pin "3") (pinfunction "3_3") (pintype "passive"))
      (node (ref "U1") (pin "12") (pinfunction "B2_12") (pintype "passive"))
    )
    (net (code "75") (name "Net-(U1-B3)") (class "Default")
      (node (ref "P7") (pin "3") (pinfunction "3_3") (pintype "passive"))
      (node (ref "U1") (pin "11") (pinfunction "B3_11") (pintype "passive"))
    )
    (net (code "76") (name "Net-(U1-B4)") (class "Default")
      (node (ref "P8") (pin "3") (pinfunction "3_3") (pintype "passive"))
      (node (ref "U1") (pin "10") (pinfunction "B4_10") (pintype "passive"))
    )
    (net (code "77") (name "Net-(U5-CPOUT)") (class "Default")
      (node (ref "C13") (pin "2") (pinfunction "2_2") (pintype "passive"))
      (node (ref "U5") (pin "20") (pinfunction "CPOUT_20") (pintype "passive"))
    )
    (net (code "78") (name "Net-(U5-REGOUT)") (class "Default")
      (node (ref "C7") (pin "2") (pinfunction "2_2") (pintype "passive"))
      (node (ref "U5") (pin "10") (pinfunction "REGOUT_10") (pintype "passive"))
    )
    (net (code "79") (name "Net-(U13-C1)") (class "Default")
      (node (ref "C10") (pin "1") (pinfunction "1_1") (pintype "passive"))
      (node (ref "U13") (pin "10") (pinfunction "C1_10") (pintype "passive"))
    )
    (net (code "80") (name "Net-(U13-SETC)") (class "Default")
      (node (ref "C8") (pin "2") (pinfunction "2_2") (pintype "passive"))
      (node (ref "U13") (pin "12") (pinfunction "SETC_12") (pintype "passive"))
    )
    (net (code "81") (name "Net-(U13-SETP)") (class "Default")
      (node (ref "C8") (pin "1") (pinfunction "1_1") (pintype "passive"))
      (node (ref "U13") (pin "8") (pinfunction "SETP_8") (pintype "passive"))
    )
    (net (code "82") (name "unconnected-(P9-Pad4)") (class "Default")
      (node (ref "P9") (pin "4") (pinfunction "4_4") (pintype "passive"))
    )
    (net (code "83") (name "unconnected-(P9-Pad5)") (class "Default")
      (node (ref "P9") (pin "5") (pinfunction "5_5") (pintype "passive"))
    )
    (net (code "84") (name "unconnected-(P20-Pad3)") (class "Default")
      (node (ref "P20") (pin "3") (pinfunction "3_3") (pintype "passive"))
    )
    (net (code "85") (name "unconnected-(U1-NC-Pad6)") (class "Default")
      (node (ref "U1") (pin "6") (pinfunction "NC_6") (pintype "passive"))
    )
    (net (code "86") (name "unconnected-(U1-NC-Pad9)") (class "Default")
      (node (ref "U1") (pin "9") (pinfunction "NC_9") (pintype "passive"))
    )
    (net (code "87") (name "unconnected-(U2-BP-Pad4)") (class "Default")
      (node (ref "U2") (pin "4") (pinfunction "BP_4") (pintype "passive"))
    )
    (net (code "88") (name "unconnected-(U5-AUX_CL-Pad7)") (class "Default")
      (node (ref "U5") (pin "7") (pinfunction "AUX_CL_7") (pintype "passive"))
    )
    (net (code "89") (name "unconnected-(U5-AUX_DA-Pad6)") (class "Default")
      (node (ref "U5") (pin "6") (pinfunction "AUX_DA_6") (pintype "passive"))
    )
    (net (code "90") (name "unconnected-(U5-CLKOUT-Pad22)") (class "Default")
      (node (ref "U5") (pin "22") (pinfunction "CLKOUT_22") (pintype "passive"))
    )
    (net (code "91") (name "unconnected-(U5-NC1-Pad2)") (class "Default")
      (node (ref "U5") (pin "2") (pinfunction "NC1_2") (pintype "passive"))
    )
    (net (code "92") (name "unconnected-(U5-NC2-Pad3)") (class "Default")
      (node (ref "U5") (pin "3") (pinfunction "NC2_3") (pintype "passive"))
    )
    (net (code "93") (name "unconnected-(U5-NC3-Pad4)") (class "Default")
      (node (ref "U5") (pin "4") (pinfunction "NC3_4") (pintype "passive"))
    )
    (net (code "94") (name "unconnected-(U5-NC4-Pad5)") (class "Default")
      (node (ref "U5") (pin "5") (pinfunction "NC4_5") (pintype "passive"))
    )
    (net (code "95") (name "unconnected-(U5-NC5-Pad14)") (class "Default")
      (node (ref "U5") (pin "14") (pinfunction "NC5_14") (pintype "passive"))
    )
    (net (code "96") (name "unconnected-(U5-NC6-Pad15)") (class "Default")
      (node (ref "U5") (pin "15") (pinfunction "NC6_15") (pintype "passive"))
    )
    (net (code "97") (name "unconnected-(U5-NC7-Pad16)") (class "Default")
      (node (ref "U5") (pin "16") (pinfunction "NC7_16") (pintype "passive"))
    )
    (net (code "98") (name "unconnected-(U5-NC8-Pad17)") (class "Default")
      (node (ref "U5") (pin "17") (pinfunction "NC8_17") (pintype "passive"))
    )
    (net (code "99") (name "unconnected-(U5-RESV1-Pad19)") (class "Default")
      (node (ref "U5") (pin "19") (pinfunction "RESV1_19") (pintype "passive"))
    )
    (net (code "100") (name "unconnected-(U5-RESV2-Pad21)") (class "Default")
      (node (ref "U5") (pin "21") (pinfunction "RESV2_21") (pintype "passive"))
    )
    (net (code "101") (name "unconnected-(U12-SDO-Pad6)") (class "Default")
      (node (ref "U12") (pin "6") (pinfunction "SDO_6") (pintype "passive"))
    )
    (net (code "102") (name "unconnected-(U13-DRDY-Pad15)") (class "Default")
      (node (ref "U13") (pin "15") (pinfunction "DRDY_15") (pintype "passive"))
    )
  )
)
